# rn4020.net
KiCad netlist of a schematic drawn in EAGLE
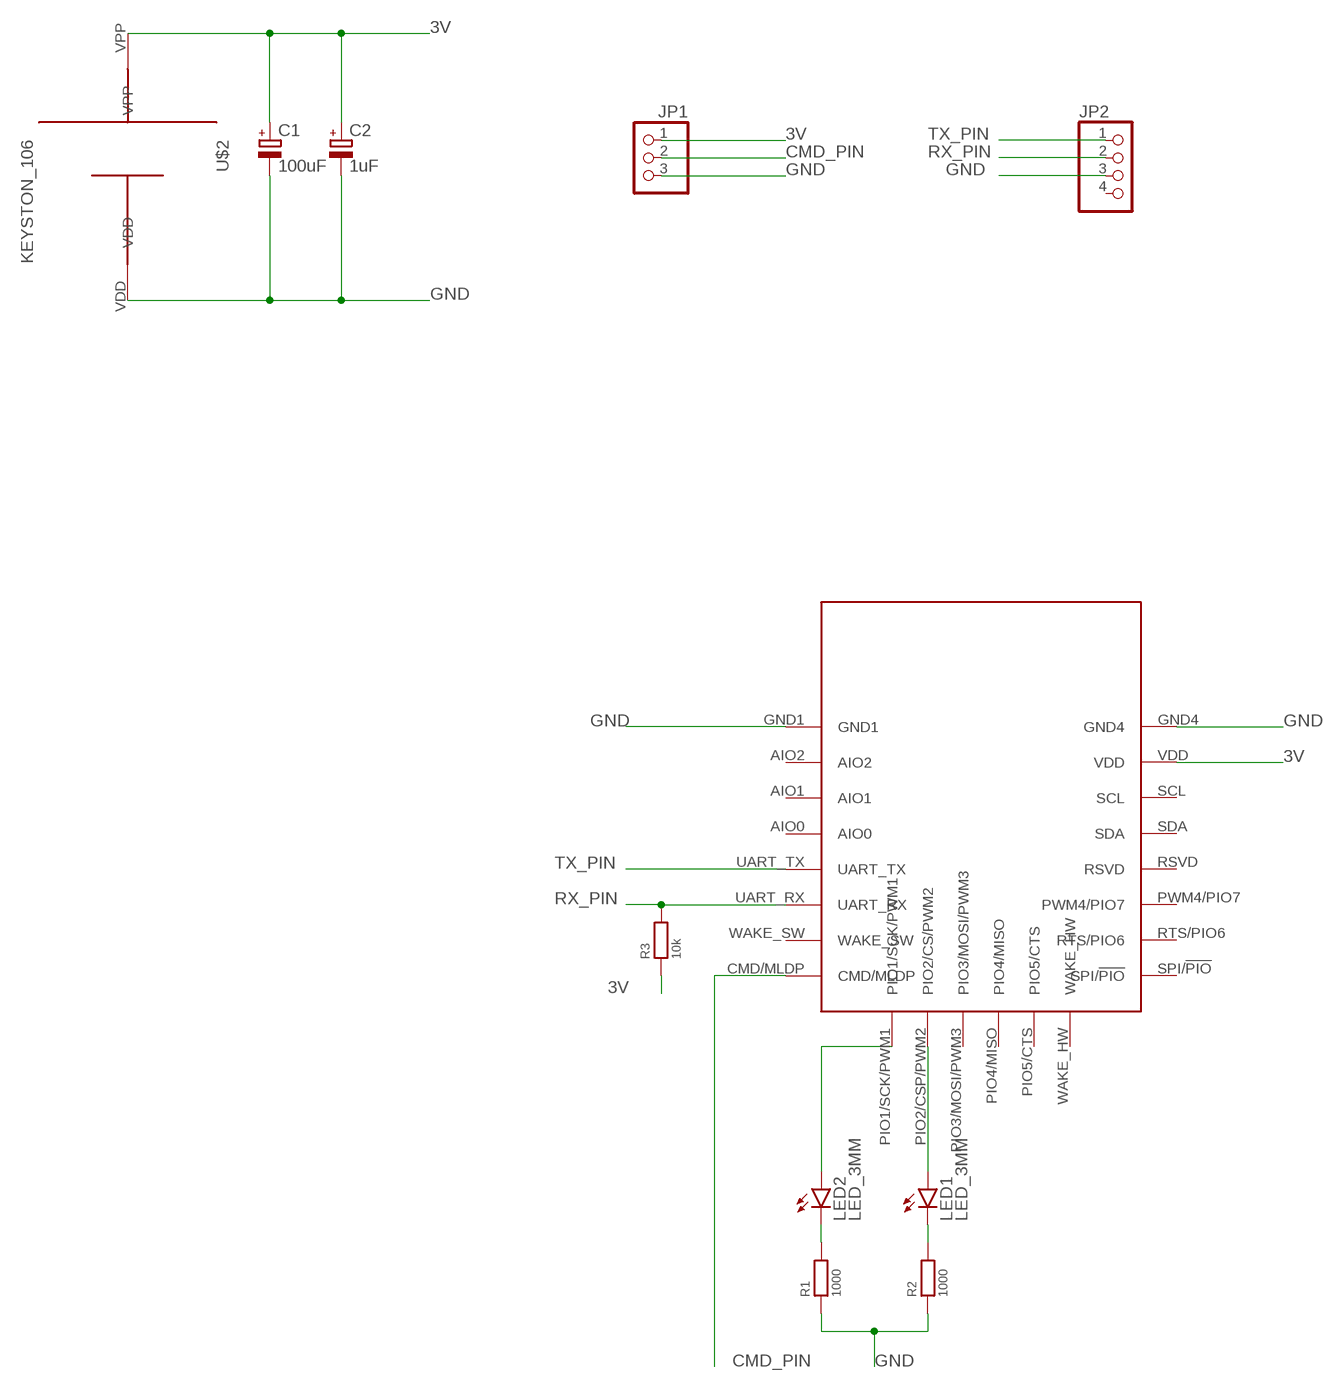
[diagram p0: schematic, sheet 1]

(export (version "E")
  (design (tool "Eeschema 10.0.6"))
  (components
    (comp (ref "C1")
      (value "100uF")
      (footprint "eagle-import:E2,5-6")
      (libsource (lib "eagle-import") (part "CPOL_DIAM5MM"))
    )
    (comp (ref "C2")
      (value "1uF")
      (footprint "eagle-import:E2,5-7")
      (libsource (lib "eagle-import") (part "CPOL_"))
    )
    (comp (ref "JP1")
      (value "PINHD-1X3")
      (footprint "eagle-import:1X03")
      (libsource (lib "eagle-import") (part "PINHD-1X3"))
    )
    (comp (ref "JP2")
      (value "PINHD-1X4")
      (footprint "eagle-import:1X04")
      (libsource (lib "eagle-import") (part "PINHD-1X4"))
    )
    (comp (ref "LED1")
      (value "LED_3MM")
      (footprint "eagle-import:LED3MM")
      (libsource (lib "eagle-import") (part "LED_3MM"))
    )
    (comp (ref "LED2")
      (value "LED_3MM")
      (footprint "eagle-import:LED3MM")
      (libsource (lib "eagle-import") (part "LED_3MM"))
    )
    (comp (ref "R1")
      (value "1000")
      (footprint "eagle-import:0207_10")
      (libsource (lib "eagle-import") (part "R_4PAS"))
    )
    (comp (ref "R2")
      (value "1000")
      (footprint "eagle-import:0207_10")
      (libsource (lib "eagle-import") (part "R_4PAS"))
    )
    (comp (ref "R3")
      (value "10k")
      (footprint "eagle-import:0207_10")
      (libsource (lib "eagle-import") (part "R_4PAS"))
    )
    (comp (ref "U$1")
      (value "RN_4020")
      (footprint "eagle-import:RN4020")
      (libsource (lib "eagle-import") (part "RN_4020"))
    )
    (comp (ref "U$2")
      (value "KEYSTON_106")
      (footprint "eagle-import:CELL_HOLDER_PACKAGE")
      (libsource (lib "eagle-import") (part "KEYSTON_106"))
    )
  )
  (nets
    (net (code "1") (name "/3V") (class "Default")
      (node (ref "C1") (pin "+") (pinfunction "P$1_+") (pintype "passive"))
      (node (ref "C2") (pin "+") (pinfunction "P$1_+") (pintype "passive"))
      (node (ref "JP1") (pin "1") (pinfunction "1_1") (pintype "passive"))
      (node (ref "R3") (pin "1") (pinfunction "P$1_1") (pintype "passive"))
      (node (ref "U$1") (pin "VDD") (pinfunction "VDD_VDD") (pintype "bidirectional"))
      (node (ref "U$2") (pin "VPP") (pinfunction "VPP_VPP") (pintype "bidirectional"))
    )
    (net (code "2") (name "/CMD_PIN") (class "Default")
      (node (ref "JP1") (pin "2") (pinfunction "2_2") (pintype "passive"))
      (node (ref "U$1") (pin "CMD/MLDP") (pinfunction "CMD/MLDP_CMD/MLDP") (pintype "bidirectional"))
    )
    (net (code "3") (name "/GND") (class "Default")
      (node (ref "C1") (pin "-") (pinfunction "P$2_-") (pintype "passive"))
      (node (ref "C2") (pin "-") (pinfunction "P$2_-") (pintype "passive"))
      (node (ref "JP1") (pin "3") (pinfunction "3_3") (pintype "passive"))
      (node (ref "JP2") (pin "3") (pinfunction "3_3") (pintype "passive"))
      (node (ref "R1") (pin "1") (pinfunction "P$1_1") (pintype "passive"))
      (node (ref "R2") (pin "1") (pinfunction "P$1_1") (pintype "passive"))
      (node (ref "U$1") (pin "GND1") (pinfunction "GND1_GND1") (pintype "bidirectional"))
      (node (ref "U$1") (pin "GND4") (pinfunction "GND4_GND4") (pintype "bidirectional"))
      (node (ref "U$2") (pin "VDD") (pinfunction "VDD_VDD") (pintype "bidirectional"))
    )
    (net (code "4") (name "/RX_PIN") (class "Default")
      (node (ref "JP2") (pin "2") (pinfunction "2_2") (pintype "passive"))
      (node (ref "R3") (pin "2") (pinfunction "P$2_2") (pintype "passive"))
      (node (ref "U$1") (pin "UART_RX") (pinfunction "UART_RX_UART_RX") (pintype "bidirectional"))
    )
    (net (code "5") (name "/TX_PIN") (class "Default")
      (node (ref "JP2") (pin "1") (pinfunction "1_1") (pintype "passive"))
      (node (ref "U$1") (pin "UART_TX") (pinfunction "UART_TX_UART_TX") (pintype "bidirectional"))
    )
    (net (code "6") (name "Net-(LED1-C)") (class "Default")
      (node (ref "LED1") (pin "K") (pinfunction "C_K") (pintype "passive"))
      (node (ref "R2") (pin "2") (pinfunction "P$2_2") (pintype "passive"))
    )
    (net (code "7") (name "Net-(LED2-C)") (class "Default")
      (node (ref "LED2") (pin "K") (pinfunction "C_K") (pintype "passive"))
      (node (ref "R1") (pin "2") (pinfunction "P$2_2") (pintype "passive"))
    )
    (net (code "8") (name "Net-(LED2-PadA)") (class "Default")
      (node (ref "LED2") (pin "A") (pinfunction "A_A") (pintype "passive"))
      (node (ref "U$1") (pin "PIO1/SCK/PWM1") (pinfunction "PIO1/SCK/PWM1_PIO1/SCK/PWM1") (pintype "bidirectional"))
    )
    (net (code "9") (name "Net-(U$1-PIO2{slash}CS{slash}PWM2)") (class "Default")
      (node (ref "LED1") (pin "A") (pinfunction "A_A") (pintype "passive"))
      (node (ref "U$1") (pin "PIO2/CSP/PWM2") (pinfunction "PIO2/CS/PWM2_PIO2/CSP/PWM2") (pintype "bidirectional"))
    )
    (net (code "10") (name "unconnected-(JP2-Pad4)") (class "Default")
      (node (ref "JP2") (pin "4") (pinfunction "4_4") (pintype "passive"))
    )
    (net (code "11") (name "unconnected-(U$1-PadAIO0)") (class "Default")
      (node (ref "U$1") (pin "AIO0") (pinfunction "AIO0_AIO0") (pintype "bidirectional"))
    )
    (net (code "12") (name "unconnected-(U$1-PadAIO1)") (class "Default")
      (node (ref "U$1") (pin "AIO1") (pinfunction "AIO1_AIO1") (pintype "bidirectional"))
    )
    (net (code "13") (name "unconnected-(U$1-PadAIO2)") (class "Default")
      (node (ref "U$1") (pin "AIO2") (pinfunction "AIO2_AIO2") (pintype "bidirectional"))
    )
    (net (code "14") (name "unconnected-(U$1-PadPIO3{slash}MOSI{slash}PWM3)") (class "Default")
      (node (ref "U$1") (pin "PIO3/MOSI/PWM3") (pinfunction "PIO3/MOSI/PWM3_PIO3/MOSI/PWM3") (pintype "bidirectional"))
    )
    (net (code "15") (name "unconnected-(U$1-PadPIO4{slash}MISO)") (class "Default")
      (node (ref "U$1") (pin "PIO4/MISO") (pinfunction "PIO4/MISO_PIO4/MISO") (pintype "bidirectional"))
    )
    (net (code "16") (name "unconnected-(U$1-PadPIO5{slash}CTS)") (class "Default")
      (node (ref "U$1") (pin "PIO5/CTS") (pinfunction "PIO5/CTS_PIO5/CTS") (pintype "bidirectional"))
    )
    (net (code "17") (name "unconnected-(U$1-PadPWM4{slash}PIO7)") (class "Default")
      (node (ref "U$1") (pin "PWM4/PIO7") (pinfunction "PWM4/PIO7_PWM4/PIO7") (pintype "bidirectional"))
    )
    (net (code "18") (name "unconnected-(U$1-PadRSVD)") (class "Default")
      (node (ref "U$1") (pin "RSVD") (pinfunction "RSVD_RSVD") (pintype "bidirectional"))
    )
    (net (code "19") (name "unconnected-(U$1-PadRTS{slash}PIO6)") (class "Default")
      (node (ref "U$1") (pin "RTS/PIO6") (pinfunction "RTS/PIO6_RTS/PIO6") (pintype "bidirectional"))
    )
    (net (code "20") (name "unconnected-(U$1-PadSCL)") (class "Default")
      (node (ref "U$1") (pin "SCL") (pinfunction "SCL_SCL") (pintype "bidirectional"))
    )
    (net (code "21") (name "unconnected-(U$1-PadSDA)") (class "Default")
      (node (ref "U$1") (pin "SDA") (pinfunction "SDA_SDA") (pintype "bidirectional"))
    )
    (net (code "22") (name "unconnected-(U$1-PadWAKE_HW)") (class "Default")
      (node (ref "U$1") (pin "WAKE_HW") (pinfunction "WAKE_HW_WAKE_HW") (pintype "bidirectional"))
    )
    (net (code "23") (name "unconnected-(U$1-PadWAKE_SW)") (class "Default")
      (node (ref "U$1") (pin "WAKE_SW") (pinfunction "WAKE_SW_WAKE_SW") (pintype "bidirectional"))
    )
    (net (code "24") (name "unconnected-(U$1-SPI{slash}~{PIO}-PadSPI{slash}!PIO)") (class "Default")
      (node (ref "U$1") (pin "SPI/!PIO") (pinfunction "SPI/~{PIO}_SPI/!PIO") (pintype "bidirectional"))
    )
  )
)
